# BlinkyBoard.net
KiCad netlist of a schematic drawn in EAGLE
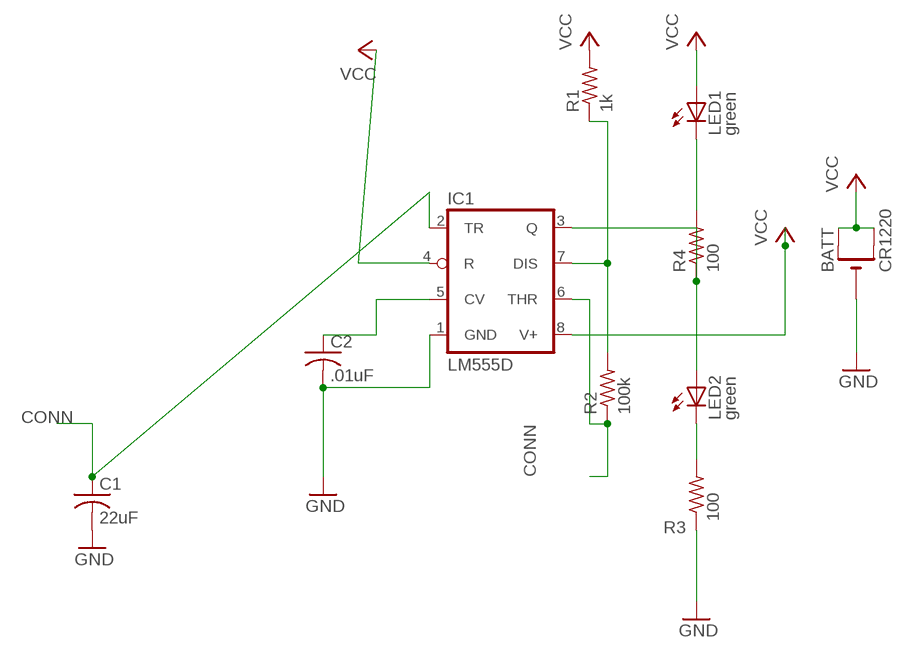
[diagram p0: schematic, sheet 1]

(export (version "E")
  (design (tool "Eeschema 10.0.6"))
  (components
    (comp (ref "BATT")
      (value "CR1220")
      (footprint "eagle-import:CR1220-SMD")
      (libsource (lib "eagle-import") (part "CR1220SMT"))
    )
    (comp (ref "C1")
      (value "22uF")
      (footprint "eagle-import:C0805")
      (fields (field (name "MF") "KEMET") (field (name "MPN") "CDR31BX103AKZS"))
      (libsource (lib "eagle-import") (part "C-USC0805"))
    )
    (comp (ref "C2")
      (value ".01uF")
      (footprint "eagle-import:C0805")
      (fields (field (name "MF") "VISHAY") (field (name "MPN") "MKT1813422635G"))
      (libsource (lib "eagle-import") (part "C-USC0805"))
    )
    (comp (ref "IC1")
      (value "LM555D")
      (footprint "eagle-import:SO08")
      (fields (field (name "MF") "TEXAS INSTRUMENTS") (field (name "MPN") "TLC555CP"))
      (libsource (lib "eagle-import") (part "555DLM"))
    )
    (comp (ref "LED1")
      (value "green")
      (footprint "eagle-import:CHIPLED_0805")
      (fields (field (name "MF") "LUMEX") (field (name "MPN") "SML-LX0805GC-TR"))
      (libsource (lib "eagle-import") (part "LEDCHIPLED_0805"))
    )
    (comp (ref "LED2")
      (value "green")
      (footprint "eagle-import:CHIPLED_0805")
      (fields (field (name "MF") "LUMEX") (field (name "MPN") "SML-LX0805GC-TR"))
      (libsource (lib "eagle-import") (part "LEDCHIPLED_0805"))
    )
    (comp (ref "R1")
      (value "1k")
      (footprint "eagle-import:R0805")
      (fields (field (name "MF") "HONEYWELL") (field (name "MPN") "700-102AAB-B00"))
      (libsource (lib "eagle-import") (part "R-US_R0805"))
    )
    (comp (ref "R2")
      (value "100k")
      (footprint "eagle-import:R0805")
      (fields (field (name "MF") "VISHAY") (field (name "MPN") "CRCW0805100RJNEA"))
      (libsource (lib "eagle-import") (part "R-US_R0805"))
    )
    (comp (ref "R3")
      (value "100")
      (footprint "eagle-import:R0805")
      (fields (field (name "MF") "NEOHM - TE CONNECTIVITY") (field (name "MPN") "1614883-1"))
      (libsource (lib "eagle-import") (part "R-US_R0805"))
    )
    (comp (ref "R4")
      (value "100")
      (footprint "eagle-import:R0805")
      (fields (field (name "MF") "NEOHM - TE CONNECTIVITY") (field (name "MPN") "1614883-1"))
      (libsource (lib "eagle-import") (part "R-US_R0805"))
    )
  )
  (nets
    (net (code "1") (name "/CONN") (class "Default")
      (node (ref "C1") (pin "1") (pinfunction "1_1") (pintype "passive"))
      (node (ref "IC1") (pin "2") (pinfunction "TR_2") (pintype "input"))
      (node (ref "IC1") (pin "6") (pinfunction "THR_6") (pintype "input"))
      (node (ref "R2") (pin "1") (pinfunction "1_1") (pintype "passive"))
    )
    (net (code "2") (name "GND") (class "Default")
      (node (ref "BATT") (pin "-") (pinfunction "-_-") (pintype "passive"))
      (node (ref "C1") (pin "2") (pinfunction "2_2") (pintype "passive"))
      (node (ref "C2") (pin "2") (pinfunction "2_2") (pintype "passive"))
      (node (ref "IC1") (pin "1") (pinfunction "GND_1") (pintype "power_in"))
      (node (ref "R3") (pin "1") (pinfunction "1_1") (pintype "passive"))
    )
    (net (code "3") (name "Net-(IC1-CV)") (class "Default")
      (node (ref "C2") (pin "1") (pinfunction "1_1") (pintype "passive"))
      (node (ref "IC1") (pin "5") (pinfunction "CV_5") (pintype "input"))
    )
    (net (code "4") (name "Net-(IC1-DIS)") (class "Default")
      (node (ref "IC1") (pin "7") (pinfunction "DIS_7") (pintype "input"))
      (node (ref "R1") (pin "1") (pinfunction "1_1") (pintype "passive"))
      (node (ref "R2") (pin "2") (pinfunction "2_2") (pintype "passive"))
    )
    (net (code "5") (name "Net-(IC1-Q)") (class "Default")
      (node (ref "IC1") (pin "3") (pinfunction "Q_3") (pintype "output"))
      (node (ref "LED2") (pin "A") (pinfunction "A_A") (pintype "passive"))
      (node (ref "R4") (pin "1") (pinfunction "1_1") (pintype "passive"))
    )
    (net (code "6") (name "Net-(LED1-PadC)") (class "Default")
      (node (ref "LED1") (pin "C") (pinfunction "C_C") (pintype "passive"))
      (node (ref "R4") (pin "2") (pinfunction "2_2") (pintype "passive"))
    )
    (net (code "7") (name "Net-(LED2-PadC)") (class "Default")
      (node (ref "LED2") (pin "C") (pinfunction "C_C") (pintype "passive"))
      (node (ref "R3") (pin "2") (pinfunction "2_2") (pintype "passive"))
    )
    (net (code "8") (name "VCC") (class "Default")
      (node (ref "BATT") (pin "+$1") (pinfunction "+_+$1") (pintype "passive"))
      (node (ref "BATT") (pin "+$2") (pinfunction "+1_+$2") (pintype "passive"))
      (node (ref "IC1") (pin "4") (pinfunction "R_4") (pintype "input"))
      (node (ref "IC1") (pin "8") (pinfunction "V+_8") (pintype "power_in"))
      (node (ref "LED1") (pin "A") (pinfunction "A_A") (pintype "passive"))
      (node (ref "R1") (pin "2") (pinfunction "2_2") (pintype "passive"))
    )
  )
)
